# DAC_DifferenceAmp.net
KiCad netlist of a schematic drawn in Altium Designer
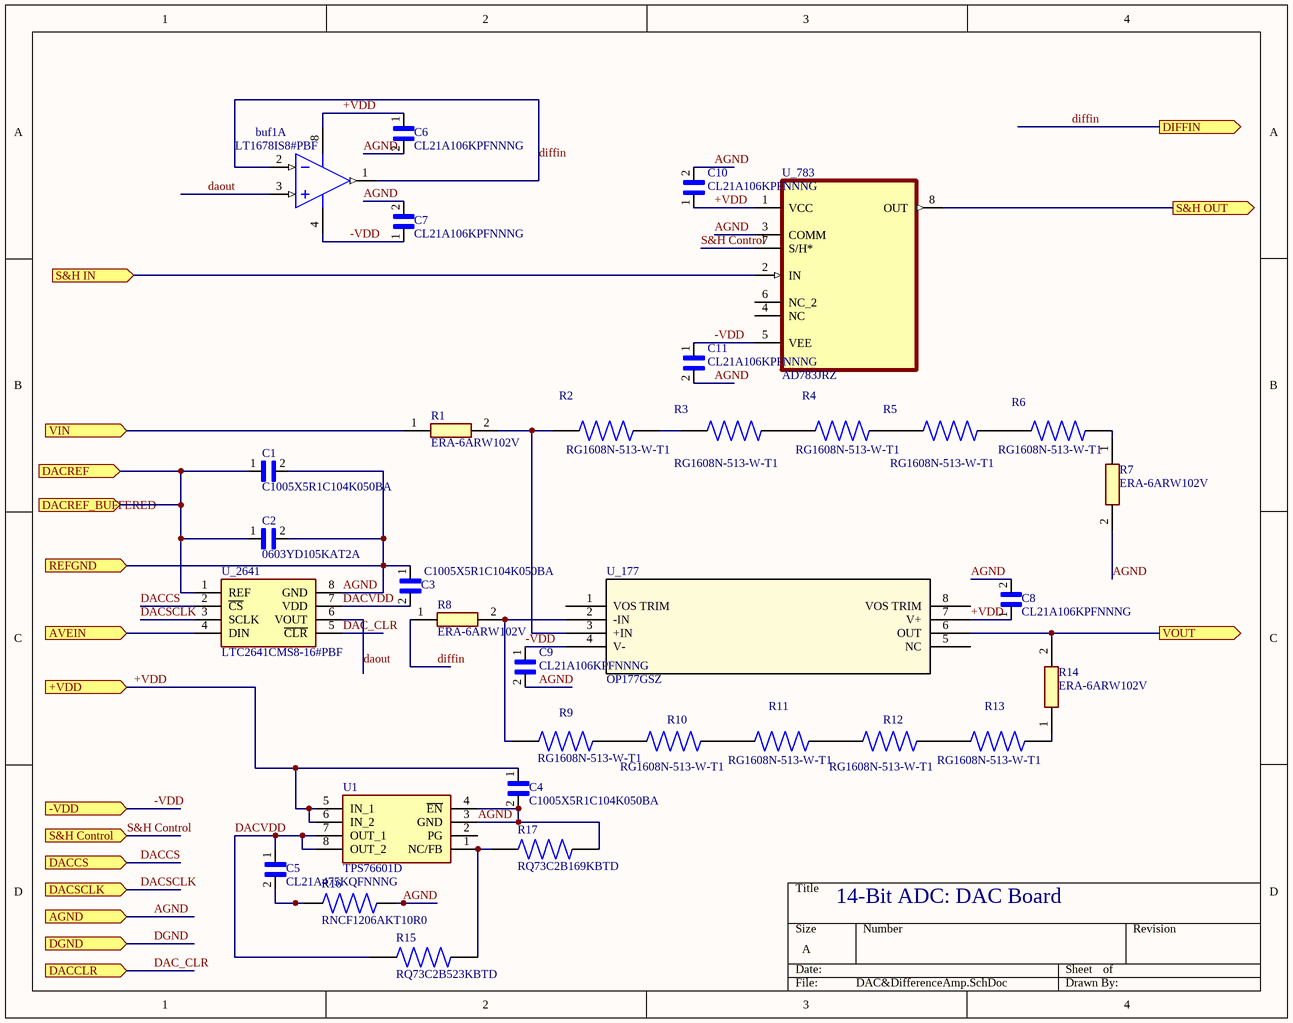
[diagram p0: DAC&DifferenceAmp.SchDoc]

(export (version "E")
  (design (tool "Eeschema 10.0.6"))
  (components
    (comp (ref "buf1")
      (value "LT1678IS8#PBF")
      (footprint "LT-S8-8_L")
      (fields
        (field (name "LINEAR TECHNOLOGY PART NUMBER") "LT1678")
        (field (name "MANUFACTURER") "Linear Technology")
      )
      (libsource (lib "Altium Content Vault") (part "LT-LT1678-S8-8"))
    )
    (comp (ref "C1")
      (value "C1005X5R1C104K050BA")
      (footprint "CAPC1005X55N")
      (description "CERAMIC CAPACITOR, 0.1UF, 16V, X5R, 10%, 0402")
      (libsource (lib "C1005X5R1C104K050BA") (part "C1005X5R1C104K050BA"))
    )
    (comp (ref "C2")
      (value "0603YD105KAT2A")
      (footprint "CAPC1608X90N")
      (description "1ÂµF Â±10% 16V Ceramic Capacitor X5R 0603 (1608 Metric)")
      (fields (field (name "MF") "AVX"))
      (libsource (lib "0603YD105KAT2A") (part "0603YD105KAT2A"))
    )
    (comp (ref "C3")
      (value "C1005X5R1C104K050BA")
      (footprint "CAPC1005X55N")
      (description "CERAMIC CAPACITOR, 0.1UF, 16V, X5R, 10%, 0402")
      (libsource (lib "") (part "C1005X5R1C104K050BA_1"))
    )
    (comp (ref "C4")
      (value "C1005X5R1C104K050BA")
      (footprint "CAPC1005X55N")
      (description "CERAMIC CAPACITOR, 0.1UF, 16V, X5R, 10%, 0402")
      (libsource (lib "") (part "C1005X5R1C104K050BA_1"))
    )
    (comp (ref "C5")
      (value "CL21A475KQFNNNG")
      (footprint "CAPC2012X135N")
      (description "4.7U 6.3V K0805 X5R")
      (libsource (lib "CL21A475KQFNNNG") (part "CL21A475KQFNNNG"))
    )
    (comp (ref "C6")
      (value "CL21A106KPFNNNG")
      (footprint "CAPC2012X135N")
      (description "10ÂµF Â±10% 10V Ceramic Capacitor X5R 0805 (2012 Metric)")
      (fields
        (field (name "MF") "Samsung Electro-Mechanics")
        (field (name "DIGI-KEY_PART_NUMBER") "1276-6456-1-ND")
      )
      (libsource (lib "CL21A106KPFNNNG") (part "CL21A106KPFNNNG"))
    )
    (comp (ref "C7")
      (value "CL21A106KPFNNNG")
      (footprint "CAPC2012X135N")
      (description "10ÂµF Â±10% 10V Ceramic Capacitor X5R 0805 (2012 Metric)")
      (fields
        (field (name "MF") "Samsung Electro-Mechanics")
        (field (name "DIGI-KEY_PART_NUMBER") "1276-6456-1-ND")
      )
      (libsource (lib "") (part "CL21A106KPFNNNG_1"))
    )
    (comp (ref "C8")
      (value "CL21A106KPFNNNG")
      (footprint "CAPC2012X135N")
      (description "10ÂµF Â±10% 10V Ceramic Capacitor X5R 0805 (2012 Metric)")
      (fields
        (field (name "MF") "Samsung Electro-Mechanics")
        (field (name "DIGI-KEY_PART_NUMBER") "1276-6456-1-ND")
      )
      (libsource (lib "") (part "CL21A106KPFNNNG_1"))
    )
    (comp (ref "C9")
      (value "CL21A106KPFNNNG")
      (footprint "CAPC2012X135N")
      (description "10ÂµF Â±10% 10V Ceramic Capacitor X5R 0805 (2012 Metric)")
      (fields
        (field (name "MF") "Samsung Electro-Mechanics")
        (field (name "DIGI-KEY_PART_NUMBER") "1276-6456-1-ND")
      )
      (libsource (lib "CL21A106KPFNNNG") (part "CL21A106KPFNNNG"))
    )
    (comp (ref "C10")
      (value "CL21A106KPFNNNG")
      (footprint "CAPC2012X135N")
      (description "10ÂµF Â±10% 10V Ceramic Capacitor X5R 0805 (2012 Metric)")
      (fields
        (field (name "MF") "Samsung Electro-Mechanics")
        (field (name "DIGI-KEY_PART_NUMBER") "1276-6456-1-ND")
      )
      (libsource (lib "") (part "CL21A106KPFNNNG_1"))
    )
    (comp (ref "C11")
      (value "CL21A106KPFNNNG")
      (footprint "CAPC2012X135N")
      (description "10ÂµF Â±10% 10V Ceramic Capacitor X5R 0805 (2012 Metric)")
      (fields
        (field (name "MF") "Samsung Electro-Mechanics")
        (field (name "DIGI-KEY_PART_NUMBER") "1276-6456-1-ND")
      )
      (libsource (lib "CL21A106KPFNNNG") (part "CL21A106KPFNNNG"))
    )
    (comp (ref "R1")
      (value "ERA-6ARW102V")
      (footprint "SamacSys:ERA6A_(0805)")
      (description "Resistor")
      (libsource (lib "*") (part "ERA-6ARW102V"))
    )
    (comp (ref "R2")
      (value "RG1608N-513-W-T1")
      (footprint "RESC1608X50N")
      (libsource (lib "RG1608N-513-W-T1") (part "RG1608N-513-W-T1"))
    )
    (comp (ref "R3")
      (value "RG1608N-513-W-T1")
      (footprint "RESC1608X50N")
      (libsource (lib "RG1608N-513-W-T1") (part "RG1608N-513-W-T1"))
    )
    (comp (ref "R4")
      (value "RG1608N-513-W-T1")
      (footprint "RESC1608X50N")
      (libsource (lib "RG1608N-513-W-T1") (part "RG1608N-513-W-T1"))
    )
    (comp (ref "R5")
      (value "RG1608N-513-W-T1")
      (footprint "RESC1608X50N")
      (libsource (lib "RG1608N-513-W-T1") (part "RG1608N-513-W-T1"))
    )
    (comp (ref "R6")
      (value "RG1608N-513-W-T1")
      (footprint "RESC1608X50N")
      (libsource (lib "RG1608N-513-W-T1") (part "RG1608N-513-W-T1"))
    )
    (comp (ref "R7")
      (value "ERA-6ARW102V")
      (footprint "SamacSys:ERA6A_(0805)")
      (description "Resistor")
      (libsource (lib "") (part "ERA-6ARW102V_1"))
    )
    (comp (ref "R8")
      (value "ERA-6ARW102V")
      (footprint "SamacSys:ERA6A_(0805)")
      (description "Resistor")
      (libsource (lib "*") (part "ERA-6ARW102V"))
    )
    (comp (ref "R9")
      (value "RG1608N-513-W-T1")
      (footprint "RESC1608X50N")
      (libsource (lib "RG1608N-513-W-T1") (part "RG1608N-513-W-T1"))
    )
    (comp (ref "R10")
      (value "RG1608N-513-W-T1")
      (footprint "RESC1608X50N")
      (libsource (lib "RG1608N-513-W-T1") (part "RG1608N-513-W-T1"))
    )
    (comp (ref "R11")
      (value "RG1608N-513-W-T1")
      (footprint "RESC1608X50N")
      (libsource (lib "RG1608N-513-W-T1") (part "RG1608N-513-W-T1"))
    )
    (comp (ref "R12")
      (value "RG1608N-513-W-T1")
      (footprint "RESC1608X50N")
      (libsource (lib "RG1608N-513-W-T1") (part "RG1608N-513-W-T1"))
    )
    (comp (ref "R13")
      (value "RG1608N-513-W-T1")
      (footprint "RESC1608X50N")
      (libsource (lib "RG1608N-513-W-T1") (part "RG1608N-513-W-T1"))
    )
    (comp (ref "R14")
      (value "ERA-6ARW102V")
      (footprint "SamacSys:ERA6A_(0805)")
      (description "Resistor")
      (libsource (lib "") (part "ERA-6ARW102V_2"))
    )
    (comp (ref "R15")
      (value "RQ73C2B523KBTD")
      (footprint "RESC3116X75N")
      (libsource (lib "RQ73C2B523KBTD") (part "RQ73C2B523KBTD"))
    )
    (comp (ref "R16")
      (value "RNCF1206AKT10R0")
      (footprint "RESC3015X65N")
      (libsource (lib "RNCF1206AKT10R0") (part "RNCF1206AKT10R0"))
    )
    (comp (ref "R17")
      (value "RQ73C2B169KBTD")
      (footprint "RESC3116X75N")
      (libsource (lib "RQ73C2B169KBTD") (part "RQ73C2B169KBTD"))
    )
    (comp (ref "U1")
      (value "TPS76601D")
      (footprint "SamacSys:SOIC127P600X175-8N")
      (description "Integrated Circuit")
      (fields (field (name "MOUSER PART NUMBER") "595-TPS76601D"))
      (libsource (lib "*") (part "TPS76601D"))
    )
    (comp (ref "U_177")
      (value "OP177GSZ")
      (footprint "R_8_ADI")
      (description "No Description Available")
      (fields (field (name "COPYRIGHT") "Copyright (C) 2021 Accelerated Designs. All rights reserved"))
      (libsource (lib "OP177GSZ") (part "OP177GSZ"))
    )
    (comp (ref "U_783")
      (value "AD783JRZ")
      (footprint "SOIC127P600X272-8N")
      (description "Sample and Hold Amplifier 1 Circuit 8-SOIC")
      (fields (field (name "MF") "Analog Devices"))
      (libsource (lib "AD783JRZ") (part "AD783JRZ"))
    )
    (comp (ref "U_2641")
      (value "LTC2641CMS8-16#PBF")
      (footprint "SamacSys:SOP65P490X110-8N")
      (description "Integrated Circuit")
      (fields (field (name "MOUSER PART NUMBER") "584-C2641CMS8-16PBF"))
      (libsource (lib "*") (part "LTC2641CMS8-16#PBF"))
    )
  )
  (nets
    (net (code "1") (name "/+VDD") (class "Default")
      (node (ref "C10") (pin "1") (pinfunction "1_1") (pintype "passive"))
      (node (ref "C4") (pin "1") (pinfunction "1_1") (pintype "passive"))
      (node (ref "C6") (pin "1") (pinfunction "1_1") (pintype "passive"))
      (node (ref "C8") (pin "1") (pinfunction "1_1") (pintype "passive"))
      (node (ref "U1") (pin "5") (pinfunction "IN_1_5") (pintype "passive"))
      (node (ref "U1") (pin "6") (pinfunction "IN_2_6") (pintype "passive"))
      (node (ref "U_177") (pin "7") (pinfunction "V+_7") (pintype "power_in"))
      (node (ref "U_783") (pin "1") (pinfunction "VCC_1") (pintype "power_in"))
      (node (ref "buf1") (pin "8") (pinfunction "V+_8") (pintype "power_in"))
    )
    (net (code "2") (name "/-VDD") (class "Default")
      (node (ref "C11") (pin "1") (pinfunction "1_1") (pintype "passive"))
      (node (ref "C7") (pin "1") (pinfunction "1_1") (pintype "passive"))
      (node (ref "C9") (pin "1") (pinfunction "1_1") (pintype "passive"))
      (node (ref "U_177") (pin "4") (pinfunction "V-_4") (pintype "power_in"))
      (node (ref "U_783") (pin "5") (pinfunction "VEE_5") (pintype "power_in"))
      (node (ref "buf1") (pin "4") (pinfunction "V-_4") (pintype "power_in"))
    )
    (net (code "3") (name "/AGND") (class "Default")
      (node (ref "C1") (pin "2") (pinfunction "2_2") (pintype "passive"))
      (node (ref "C10") (pin "2") (pinfunction "2_2") (pintype "passive"))
      (node (ref "C11") (pin "2") (pinfunction "2_2") (pintype "passive"))
      (node (ref "C2") (pin "2") (pinfunction "2_2") (pintype "passive"))
      (node (ref "C3") (pin "1") (pinfunction "1_1") (pintype "passive"))
      (node (ref "C4") (pin "2") (pinfunction "2_2") (pintype "passive"))
      (node (ref "C6") (pin "2") (pinfunction "2_2") (pintype "passive"))
      (node (ref "C7") (pin "2") (pinfunction "2_2") (pintype "passive"))
      (node (ref "C8") (pin "2") (pinfunction "2_2") (pintype "passive"))
      (node (ref "C9") (pin "2") (pinfunction "2_2") (pintype "passive"))
      (node (ref "R16") (pin "2") (pinfunction "2_2") (pintype "passive"))
      (node (ref "R17") (pin "2") (pinfunction "2_2") (pintype "passive"))
      (node (ref "R7") (pin "2") (pinfunction "2_2") (pintype "passive"))
      (node (ref "U1") (pin "3") (pinfunction "GND_3") (pintype "passive"))
      (node (ref "U1") (pin "4") (pinfunction "~{EN}_4") (pintype "passive"))
      (node (ref "U_2641") (pin "8") (pinfunction "GND_8") (pintype "passive"))
      (node (ref "U_783") (pin "3") (pinfunction "COMM_3") (pintype "passive"))
    )
    (net (code "4") (name "/AVEIN") (class "Default")
      (node (ref "U_2641") (pin "4") (pinfunction "DIN_4") (pintype "passive"))
    )
    (net (code "5") (name "/DACCS") (class "Default")
      (node (ref "U_2641") (pin "2") (pinfunction "~{CS}_2") (pintype "passive"))
    )
    (net (code "6") (name "/DACREF") (class "Default")
      (node (ref "C1") (pin "1") (pinfunction "1_1") (pintype "passive"))
      (node (ref "C2") (pin "1") (pinfunction "1_1") (pintype "passive"))
      (node (ref "U_2641") (pin "1") (pinfunction "REF_1") (pintype "passive"))
    )
    (net (code "7") (name "/DACSCLK") (class "Default")
      (node (ref "U_2641") (pin "3") (pinfunction "SCLK_3") (pintype "passive"))
    )
    (net (code "8") (name "/DACVDD") (class "Default")
      (node (ref "C3") (pin "2") (pinfunction "2_2") (pintype "passive"))
      (node (ref "C5") (pin "1") (pinfunction "1_1") (pintype "passive"))
      (node (ref "R15") (pin "1") (pinfunction "1_1") (pintype "passive"))
      (node (ref "U1") (pin "7") (pinfunction "OUT_1_7") (pintype "passive"))
      (node (ref "U1") (pin "8") (pinfunction "OUT_2_8") (pintype "passive"))
      (node (ref "U_2641") (pin "7") (pinfunction "VDD_7") (pintype "passive"))
    )
    (net (code "9") (name "/DAC_CLR") (class "Default")
      (node (ref "U_2641") (pin "5") (pinfunction "~{CLR}_5") (pintype "passive"))
    )
    (net (code "11") (name "/S&H Control") (class "Default")
      (node (ref "U_783") (pin "7") (pinfunction "S/H*_7") (pintype "passive"))
    )
    (net (code "12") (name "/S&H IN") (class "Default")
      (node (ref "U_783") (pin "2") (pinfunction "IN_2") (pintype "input"))
    )
    (net (code "13") (name "/S&H OUT") (class "Default")
      (node (ref "U_783") (pin "8") (pinfunction "OUT_8") (pintype "output"))
    )
    (net (code "14") (name "/VIN") (class "Default")
      (node (ref "R1") (pin "1") (pinfunction "1_1") (pintype "passive"))
    )
    (net (code "15") (name "/VOUT") (class "Default")
      (node (ref "R14") (pin "2") (pinfunction "2_2") (pintype "passive"))
      (node (ref "U_177") (pin "6") (pinfunction "OUT_6") (pintype "passive"))
    )
    (net (code "16") (name "/daout") (class "Default")
      (node (ref "U_2641") (pin "6") (pinfunction "VOUT_6") (pintype "passive"))
      (node (ref "buf1") (pin "3") (pinfunction "+IN_A_3") (pintype "input"))
    )
    (net (code "17") (name "/diffin") (class "Default")
      (node (ref "R8") (pin "1") (pinfunction "1_1") (pintype "passive"))
      (node (ref "buf1") (pin "1") (pinfunction "OUT_A_1") (pintype "output"))
      (node (ref "buf1") (pin "2") (pinfunction "-IN_A_2") (pintype "input"))
    )
    (net (code "18") (name "Net-(C5-Pad2)") (class "Default")
      (node (ref "C5") (pin "2") (pinfunction "2_2") (pintype "passive"))
      (node (ref "R16") (pin "1") (pinfunction "1_1") (pintype "passive"))
    )
    (net (code "19") (name "Net-(R2-Pad2)") (class "Default")
      (node (ref "R2") (pin "2") (pinfunction "2_2") (pintype "passive"))
      (node (ref "R3") (pin "1") (pinfunction "1_1") (pintype "passive"))
    )
    (net (code "20") (name "Net-(R3-Pad2)") (class "Default")
      (node (ref "R3") (pin "2") (pinfunction "2_2") (pintype "passive"))
      (node (ref "R4") (pin "1") (pinfunction "1_1") (pintype "passive"))
    )
    (net (code "21") (name "Net-(R4-Pad2)") (class "Default")
      (node (ref "R4") (pin "2") (pinfunction "2_2") (pintype "passive"))
      (node (ref "R5") (pin "1") (pinfunction "1_1") (pintype "passive"))
    )
    (net (code "22") (name "Net-(R5-Pad2)") (class "Default")
      (node (ref "R5") (pin "2") (pinfunction "2_2") (pintype "passive"))
      (node (ref "R6") (pin "1") (pinfunction "1_1") (pintype "passive"))
    )
    (net (code "23") (name "Net-(R6-Pad2)") (class "Default")
      (node (ref "R6") (pin "2") (pinfunction "2_2") (pintype "passive"))
      (node (ref "R7") (pin "1") (pinfunction "1_1") (pintype "passive"))
    )
    (net (code "24") (name "Net-(R10-Pad1)") (class "Default")
      (node (ref "R10") (pin "1") (pinfunction "1_1") (pintype "passive"))
      (node (ref "R9") (pin "2") (pinfunction "2_2") (pintype "passive"))
    )
    (net (code "25") (name "Net-(R10-Pad2)") (class "Default")
      (node (ref "R10") (pin "2") (pinfunction "2_2") (pintype "passive"))
      (node (ref "R11") (pin "1") (pinfunction "1_1") (pintype "passive"))
    )
    (net (code "26") (name "Net-(R11-Pad2)") (class "Default")
      (node (ref "R11") (pin "2") (pinfunction "2_2") (pintype "passive"))
      (node (ref "R12") (pin "1") (pinfunction "1_1") (pintype "passive"))
    )
    (net (code "27") (name "Net-(R12-Pad2)") (class "Default")
      (node (ref "R12") (pin "2") (pinfunction "2_2") (pintype "passive"))
      (node (ref "R13") (pin "1") (pinfunction "1_1") (pintype "passive"))
    )
    (net (code "28") (name "Net-(R13-Pad2)") (class "Default")
      (node (ref "R13") (pin "2") (pinfunction "2_2") (pintype "passive"))
      (node (ref "R14") (pin "1") (pinfunction "1_1") (pintype "passive"))
    )
    (net (code "29") (name "Net-(U1-NC{slash}FB)") (class "Default")
      (node (ref "R15") (pin "2") (pinfunction "2_2") (pintype "passive"))
      (node (ref "R17") (pin "1") (pinfunction "1_1") (pintype "passive"))
      (node (ref "U1") (pin "1") (pinfunction "NC/FB_1") (pintype "passive"))
    )
    (net (code "30") (name "Net-(U_177-+IN)") (class "Default")
      (node (ref "R1") (pin "2") (pinfunction "2_2") (pintype "passive"))
      (node (ref "R2") (pin "1") (pinfunction "1_1") (pintype "passive"))
      (node (ref "U_177") (pin "3") (pinfunction "+IN_3") (pintype "passive"))
    )
    (net (code "31") (name "Net-(U_177--IN)") (class "Default")
      (node (ref "R8") (pin "2") (pinfunction "2_2") (pintype "passive"))
      (node (ref "R9") (pin "1") (pinfunction "1_1") (pintype "passive"))
      (node (ref "U_177") (pin "2") (pinfunction "-IN_2") (pintype "passive"))
    )
    (net (code "32") (name "unconnected-(U1-PG-Pad2)") (class "Default")
      (node (ref "U1") (pin "2") (pinfunction "PG_2") (pintype "passive"))
    )
    (net (code "33") (name "unconnected-(U_177-NC-Pad5)") (class "Default")
      (node (ref "U_177") (pin "5") (pinfunction "NC_5") (pintype "passive"))
    )
    (net (code "34") (name "unconnected-(U_177-VOS_TRIM-Pad1)") (class "Default")
      (node (ref "U_177") (pin "1") (pinfunction "VOS_TRIM_1") (pintype "passive"))
    )
    (net (code "35") (name "unconnected-(U_177-VOS_TRIM-Pad8)") (class "Default")
      (node (ref "U_177") (pin "8") (pinfunction "VOS_TRIM_8") (pintype "power_in"))
    )
    (net (code "36") (name "unconnected-(U_783-NC-Pad4)") (class "Default")
      (node (ref "U_783") (pin "4") (pinfunction "NC_4") (pintype "passive"))
    )
    (net (code "37") (name "unconnected-(U_783-NC_2-Pad6)") (class "Default")
      (node (ref "U_783") (pin "6") (pinfunction "NC_2_6") (pintype "passive"))
    )
  )
)
